# 50Hz_GEN_LPF.net
KiCad netlist of a schematic drawn in Altium Designer
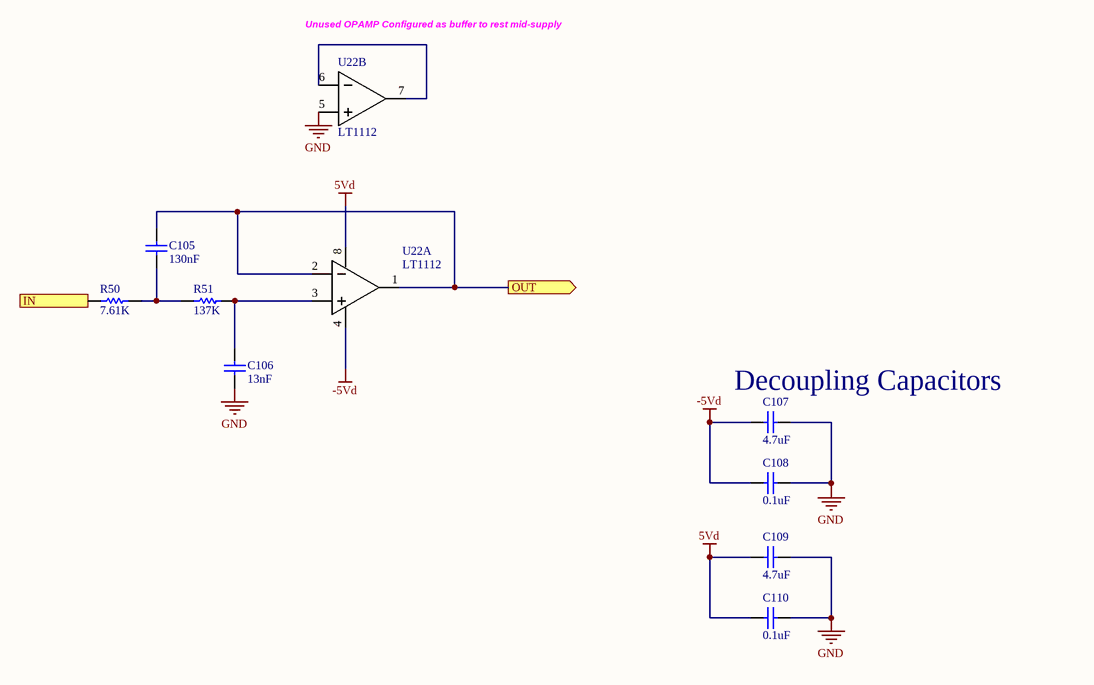
[diagram p0: 50Hz_GEN_LPF.SchDoc]

(export (version "E")
  (design (tool "Eeschema 10.0.6"))
  (components
    (comp (ref "C105")
      (value "130nF")
      (footprint "0402_Cap")
      (description "Capacitor, 16nF, 0805, 25V")
      (libsource (lib "Arturo_Approved") (part "08051C163JAT2A"))
    )
    (comp (ref "C106")
      (value "13nF")
      (footprint "0402_Cap")
      (description "Capacitor, 1.6nF, 0805, 25V")
      (libsource (lib "Arturo_Approved") (part "GRM2165C2A162JA01D"))
    )
    (comp (ref "C107")
      (value "4.7uF")
      (footprint "0402_Cap")
      (description "Capacitor, 4.7uF, 0805")
      (libsource (lib "Arturo_Approved") (part "CL21A475KAQNNNE"))
    )
    (comp (ref "C108")
      (value "0.1uF")
      (footprint "0402_Cap")
      (description "Capacitor, 0.1uF, 0805")
      (libsource (lib "Arturo_Approved") (part "CL21B104KACNNNC"))
    )
    (comp (ref "C109")
      (value "4.7uF")
      (footprint "0402_Cap")
      (description "Capacitor, 4.7uF, 0805")
      (libsource (lib "Arturo_Approved") (part "CL21A475KAQNNNE"))
    )
    (comp (ref "C110")
      (value "0.1uF")
      (footprint "0402_Cap")
      (description "Capacitor, 0.1uF, 0805")
      (libsource (lib "Arturo_Approved") (part "CL21B104KACNNNC"))
    )
    (comp (ref "R50")
      (value "7.61K")
      (footprint "0402_Res")
      (description "1.65k")
      (libsource (lib "Arturo_Approved") (part "RC0805FR-071K65L"))
    )
    (comp (ref "R51")
      (value "137K")
      (footprint "0402_Res")
      (description "5.9k")
      (libsource (lib "Arturo_Approved") (part "RC0805FR-075K9L"))
    )
    (comp (ref "U22")
      (value "LT1112")
      (footprint "SOIC_8")
      (libsource (lib "Arturo_Approved") (part "LT1112"))
    )
  )
  (nets
    (net (code "1") (name "-5Vd") (class "Default")
      (node (ref "C107") (pin "1") (pinfunction "1_1") (pintype "passive"))
      (node (ref "C108") (pin "1") (pinfunction "1_1") (pintype "passive"))
      (node (ref "U22") (pin "4") (pinfunction "4_4") (pintype "passive"))
    )
    (net (code "2") (name "/IN") (class "Default")
      (node (ref "R50") (pin "1") (pinfunction "1_1") (pintype "passive"))
    )
    (net (code "3") (name "/OUT") (class "Default")
      (node (ref "C105") (pin "2") (pinfunction "2_2") (pintype "passive"))
      (node (ref "U22") (pin "1") (pinfunction "1_1") (pintype "passive"))
      (node (ref "U22") (pin "2") (pinfunction "2_2") (pintype "passive"))
    )
    (net (code "4") (name "5Vd") (class "Default")
      (node (ref "C109") (pin "1") (pinfunction "1_1") (pintype "passive"))
      (node (ref "C110") (pin "1") (pinfunction "1_1") (pintype "passive"))
      (node (ref "U22") (pin "8") (pinfunction "8_8") (pintype "passive"))
    )
    (net (code "5") (name "GND") (class "Default")
      (node (ref "C106") (pin "1") (pinfunction "1_1") (pintype "passive"))
      (node (ref "C107") (pin "2") (pinfunction "2_2") (pintype "passive"))
      (node (ref "C108") (pin "2") (pinfunction "2_2") (pintype "passive"))
      (node (ref "C109") (pin "2") (pinfunction "2_2") (pintype "passive"))
      (node (ref "C110") (pin "2") (pinfunction "2_2") (pintype "passive"))
      (node (ref "U22") (pin "5") (pinfunction "5_5") (pintype "passive"))
    )
    (net (code "6") (name "Net-(C105-Pad1)") (class "Default")
      (node (ref "C105") (pin "1") (pinfunction "1_1") (pintype "passive"))
      (node (ref "R50") (pin "2") (pinfunction "2_2") (pintype "passive"))
      (node (ref "R51") (pin "1") (pinfunction "1_1") (pintype "passive"))
    )
    (net (code "7") (name "Net-(C106-Pad2)") (class "Default")
      (node (ref "C106") (pin "2") (pinfunction "2_2") (pintype "passive"))
      (node (ref "R51") (pin "2") (pinfunction "2_2") (pintype "passive"))
      (node (ref "U22") (pin "3") (pinfunction "3_3") (pintype "passive"))
    )
    (net (code "8") (name "Net-(U22-Pad6)") (class "Default")
      (node (ref "U22") (pin "6") (pinfunction "6_6") (pintype "passive"))
      (node (ref "U22") (pin "7") (pinfunction "7_7") (pintype "passive"))
    )
  )
)
